# 6_SWITCHING.net
KiCad netlist of a schematic drawn in Altium Designer
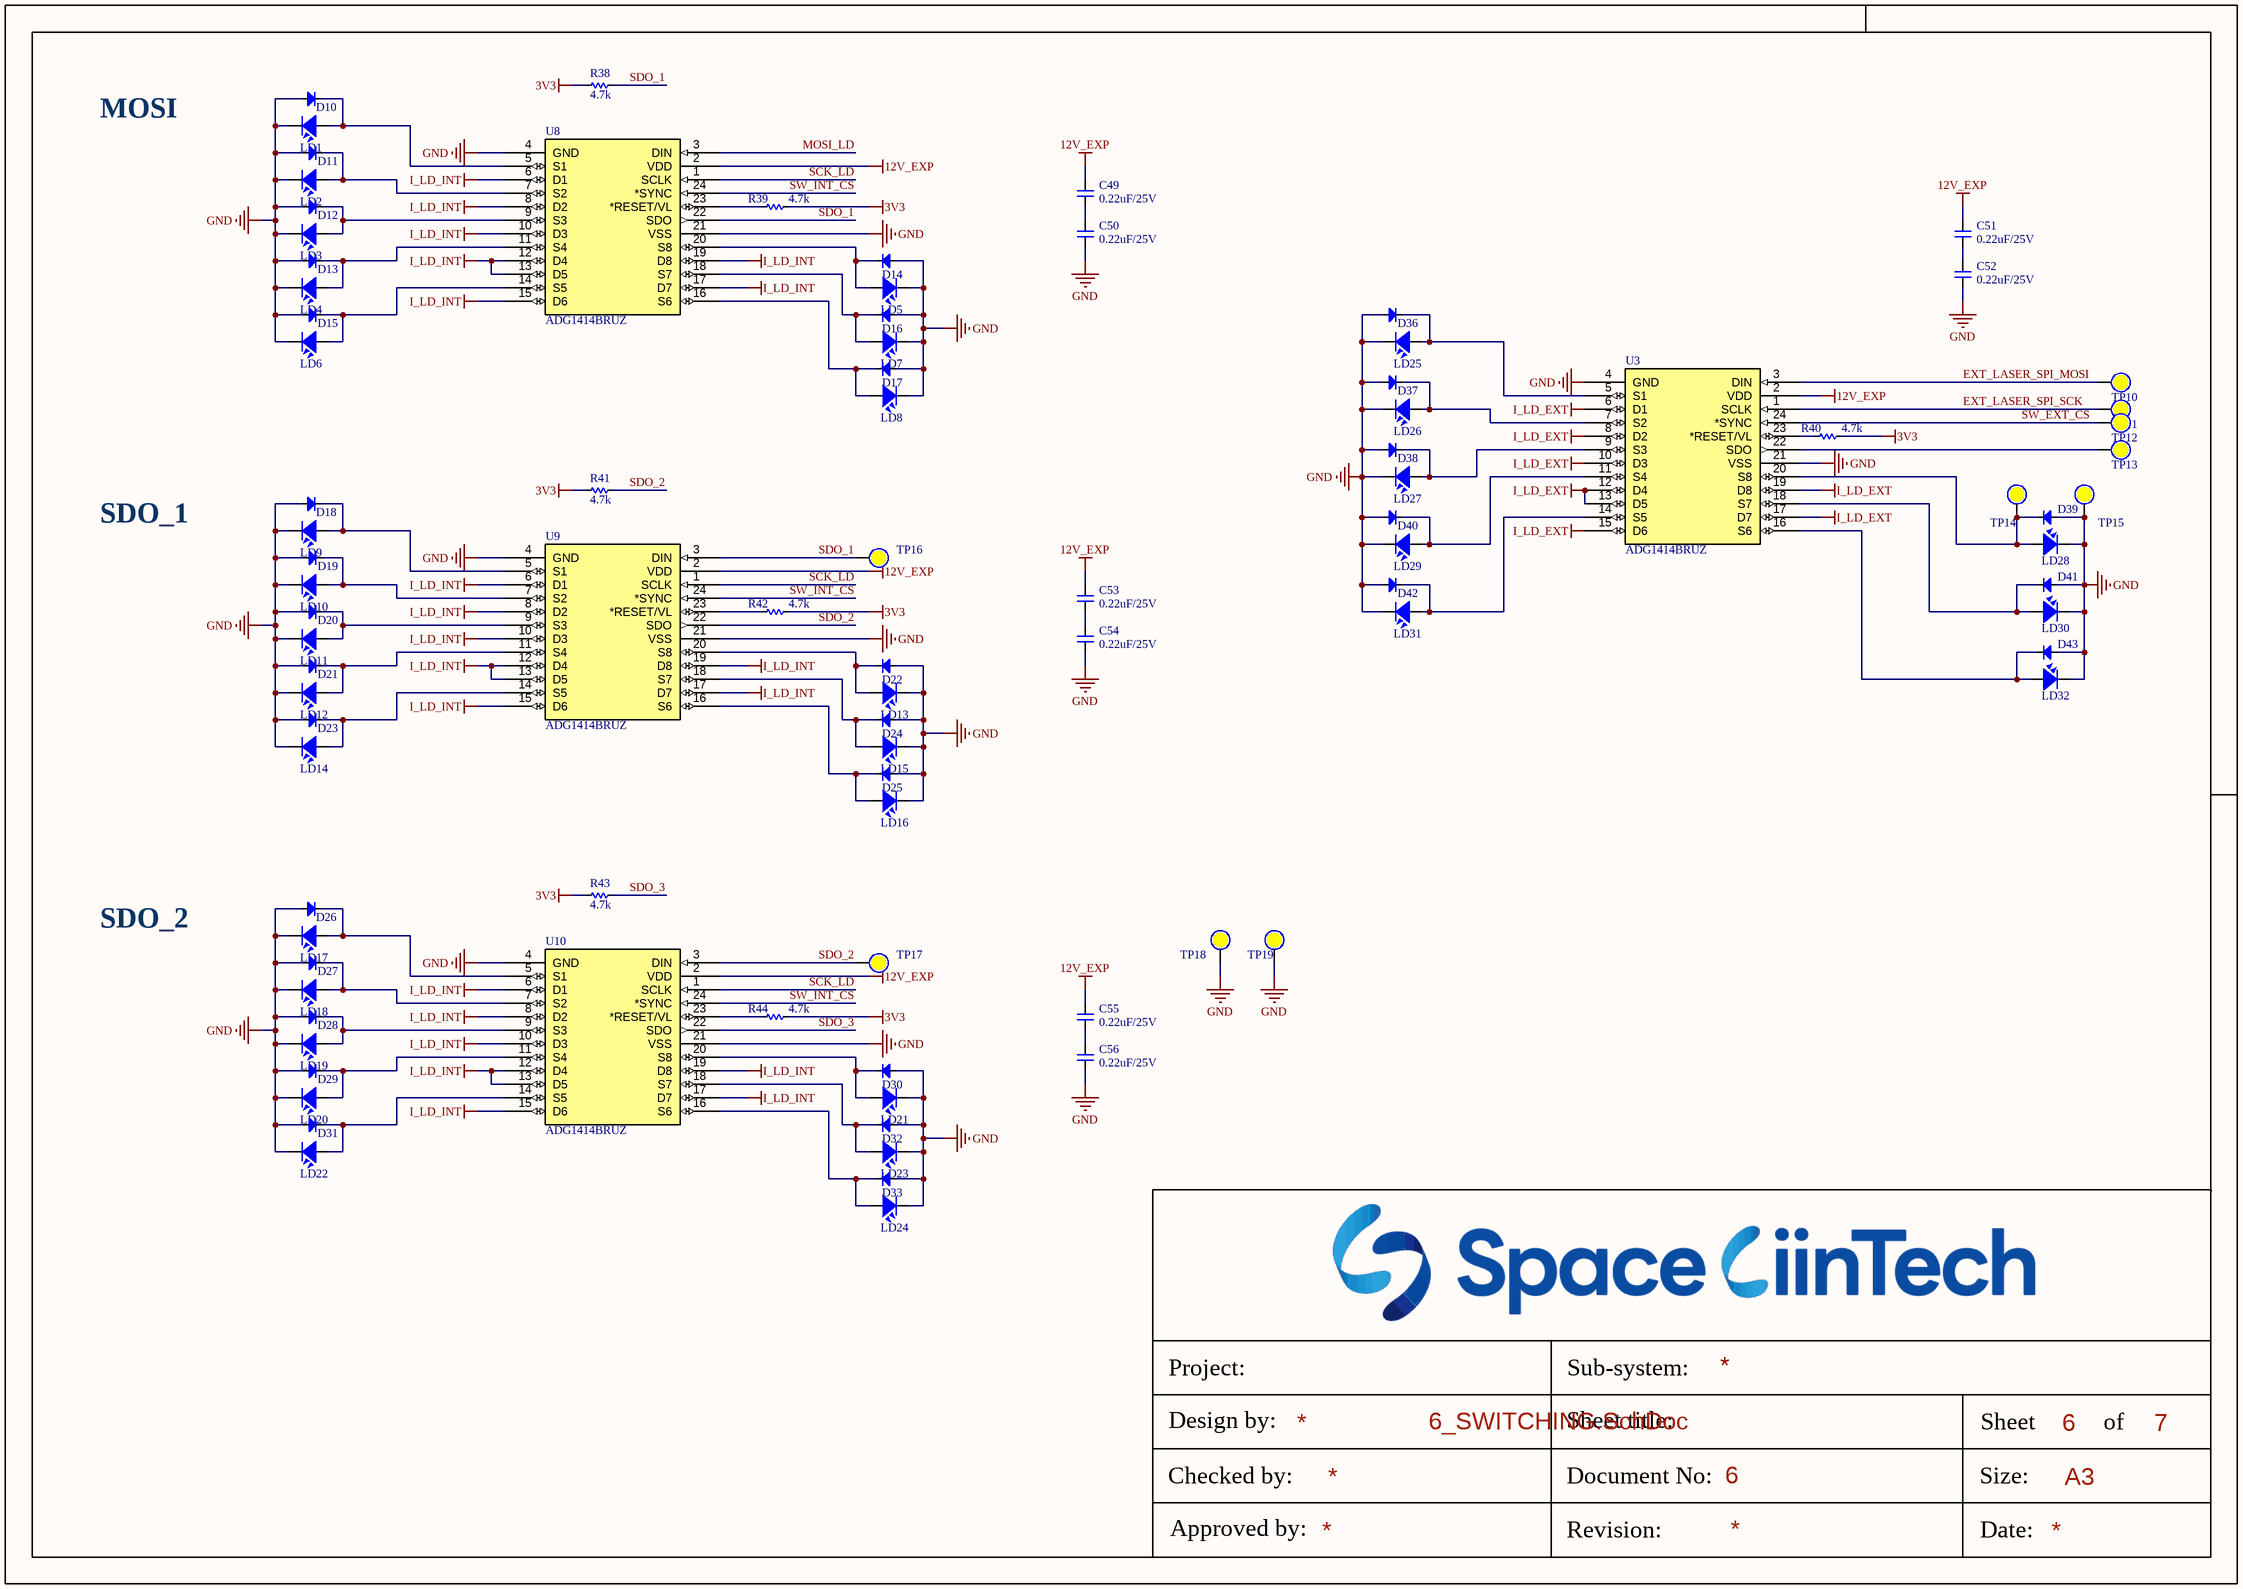
[diagram p0: 6_SWITCHING.SchDoc]

(export (version "E")
  (design (tool "Eeschema 10.0.6"))
  (components
    (comp (ref "C49")
      (value "0.22uF/25V")
      (footprint "CAP_C_1608X80")
      (description "CAP")
      (libsource (lib "LABLIB") (part "_CAP_C_2"))
    )
    (comp (ref "C50")
      (value "0.22uF/25V")
      (footprint "CAP_C_1608X80")
      (description "CAP")
      (libsource (lib "LABLIB") (part "_CAP_C_2"))
    )
    (comp (ref "C51")
      (value "0.22uF/25V")
      (footprint "CAP_C_1608X80")
      (description "CAP")
      (libsource (lib "LABLIB") (part "_CAP_C_2"))
    )
    (comp (ref "C52")
      (value "0.22uF/25V")
      (footprint "CAP_C_1608X80")
      (description "CAP")
      (libsource (lib "LABLIB") (part "_CAP_C_2"))
    )
    (comp (ref "C53")
      (value "0.22uF/25V")
      (footprint "CAP_C_1608X80")
      (description "CAP")
      (libsource (lib "LABLIB") (part "_CAP_C_2"))
    )
    (comp (ref "C54")
      (value "0.22uF/25V")
      (footprint "CAP_C_1608X80")
      (description "CAP")
      (libsource (lib "LABLIB") (part "_CAP_C_2"))
    )
    (comp (ref "C55")
      (value "0.22uF/25V")
      (footprint "CAP_C_1608X80")
      (description "CAP")
      (libsource (lib "LABLIB") (part "_CAP_C_2"))
    )
    (comp (ref "C56")
      (value "0.22uF/25V")
      (footprint "CAP_C_1608X80")
      (description "CAP")
      (libsource (lib "LABLIB") (part "_CAP_C_2"))
    )
    (comp (ref "D10")
      (value "1N4148W-TP")
      (footprint "SOD23")
      (fields (field (name "PUBLISHER") "Altium Limited"))
      (libsource (lib "LASER_LIB_SCHE") (part "Diode SMD"))
    )
    (comp (ref "D11")
      (value "1N4148W-TP")
      (footprint "SOD23")
      (fields (field (name "PUBLISHER") "Altium Limited"))
      (libsource (lib "LASER_LIB_SCHE") (part "Diode SMD"))
    )
    (comp (ref "D12")
      (value "1N4148W-TP")
      (footprint "SOD23")
      (fields (field (name "PUBLISHER") "Altium Limited"))
      (libsource (lib "LASER_LIB_SCHE") (part "Diode SMD"))
    )
    (comp (ref "D13")
      (value "1N4148W-TP")
      (footprint "SOD23")
      (fields (field (name "PUBLISHER") "Altium Limited"))
      (libsource (lib "LASER_LIB_SCHE") (part "Diode SMD"))
    )
    (comp (ref "D14")
      (value "1N4148W-TP")
      (footprint "SOD23")
      (fields (field (name "PUBLISHER") "Altium Limited"))
      (libsource (lib "LASER_LIB_SCHE") (part "Diode SMD"))
    )
    (comp (ref "D15")
      (value "1N4148W-TP")
      (footprint "SOD23")
      (fields (field (name "PUBLISHER") "Altium Limited"))
      (libsource (lib "LASER_LIB_SCHE") (part "Diode SMD"))
    )
    (comp (ref "D16")
      (value "1N4148W-TP")
      (footprint "SOD23")
      (fields (field (name "PUBLISHER") "Altium Limited"))
      (libsource (lib "LASER_LIB_SCHE") (part "Diode SMD"))
    )
    (comp (ref "D17")
      (value "1N4148W-TP")
      (footprint "SOD23")
      (fields (field (name "PUBLISHER") "Altium Limited"))
      (libsource (lib "LASER_LIB_SCHE") (part "Diode SMD"))
    )
    (comp (ref "D18")
      (value "1N4148W-TP")
      (footprint "SOD23")
      (fields (field (name "PUBLISHER") "Altium Limited"))
      (libsource (lib "LASER_LIB_SCHE") (part "Diode SMD"))
    )
    (comp (ref "D19")
      (value "1N4148W-TP")
      (footprint "SOD23")
      (fields (field (name "PUBLISHER") "Altium Limited"))
      (libsource (lib "LASER_LIB_SCHE") (part "Diode SMD"))
    )
    (comp (ref "D20")
      (value "1N4148W-TP")
      (footprint "SOD23")
      (fields (field (name "PUBLISHER") "Altium Limited"))
      (libsource (lib "LASER_LIB_SCHE") (part "Diode SMD"))
    )
    (comp (ref "D21")
      (value "1N4148W-TP")
      (footprint "SOD23")
      (fields (field (name "PUBLISHER") "Altium Limited"))
      (libsource (lib "LASER_LIB_SCHE") (part "Diode SMD"))
    )
    (comp (ref "D22")
      (value "1N4148W-TP")
      (footprint "SOD23")
      (fields (field (name "PUBLISHER") "Altium Limited"))
      (libsource (lib "LASER_LIB_SCHE") (part "Diode SMD"))
    )
    (comp (ref "D23")
      (value "1N4148W-TP")
      (footprint "SOD23")
      (fields (field (name "PUBLISHER") "Altium Limited"))
      (libsource (lib "LASER_LIB_SCHE") (part "Diode SMD"))
    )
    (comp (ref "D24")
      (value "1N4148W-TP")
      (footprint "SOD23")
      (fields (field (name "PUBLISHER") "Altium Limited"))
      (libsource (lib "LASER_LIB_SCHE") (part "Diode SMD"))
    )
    (comp (ref "D25")
      (value "1N4148W-TP")
      (footprint "SOD23")
      (fields (field (name "PUBLISHER") "Altium Limited"))
      (libsource (lib "LASER_LIB_SCHE") (part "Diode SMD"))
    )
    (comp (ref "D26")
      (value "1N4148W-TP")
      (footprint "SOD23")
      (fields (field (name "PUBLISHER") "Altium Limited"))
      (libsource (lib "LASER_LIB_SCHE") (part "Diode SMD"))
    )
    (comp (ref "D27")
      (value "1N4148W-TP")
      (footprint "SOD23")
      (fields (field (name "PUBLISHER") "Altium Limited"))
      (libsource (lib "LASER_LIB_SCHE") (part "Diode SMD"))
    )
    (comp (ref "D28")
      (value "1N4148W-TP")
      (footprint "SOD23")
      (fields (field (name "PUBLISHER") "Altium Limited"))
      (libsource (lib "LASER_LIB_SCHE") (part "Diode SMD"))
    )
    (comp (ref "D29")
      (value "1N4148W-TP")
      (footprint "SOD23")
      (fields (field (name "PUBLISHER") "Altium Limited"))
      (libsource (lib "LASER_LIB_SCHE") (part "Diode SMD"))
    )
    (comp (ref "D30")
      (value "1N4148W-TP")
      (footprint "SOD23")
      (fields (field (name "PUBLISHER") "Altium Limited"))
      (libsource (lib "LASER_LIB_SCHE") (part "Diode SMD"))
    )
    (comp (ref "D31")
      (value "1N4148W-TP")
      (footprint "SOD23")
      (fields (field (name "PUBLISHER") "Altium Limited"))
      (libsource (lib "LASER_LIB_SCHE") (part "Diode SMD"))
    )
    (comp (ref "D32")
      (value "1N4148W-TP")
      (footprint "SOD23")
      (fields (field (name "PUBLISHER") "Altium Limited"))
      (libsource (lib "LASER_LIB_SCHE") (part "Diode SMD"))
    )
    (comp (ref "D33")
      (value "1N4148W-TP")
      (footprint "SOD23")
      (fields (field (name "PUBLISHER") "Altium Limited"))
      (libsource (lib "LASER_LIB_SCHE") (part "Diode SMD"))
    )
    (comp (ref "D36")
      (value "1N4148W-TP")
      (footprint "SOD23")
      (fields (field (name "PUBLISHER") "Altium Limited"))
      (libsource (lib "LASER_LIB_SCHE") (part "Diode SMD"))
    )
    (comp (ref "D37")
      (value "1N4148W-TP")
      (footprint "SOD23")
      (fields (field (name "PUBLISHER") "Altium Limited"))
      (libsource (lib "LASER_LIB_SCHE") (part "Diode SMD"))
    )
    (comp (ref "D38")
      (value "1N4148W-TP")
      (footprint "SOD23")
      (fields (field (name "PUBLISHER") "Altium Limited"))
      (libsource (lib "LASER_LIB_SCHE") (part "Diode SMD"))
    )
    (comp (ref "D39")
      (value "1N4148W-TP")
      (footprint "SOD23")
      (fields (field (name "PUBLISHER") "Altium Limited"))
      (libsource (lib "LASER_LIB_SCHE") (part "Diode SMD"))
    )
    (comp (ref "D40")
      (value "1N4148W-TP")
      (footprint "SOD23")
      (fields (field (name "PUBLISHER") "Altium Limited"))
      (libsource (lib "LASER_LIB_SCHE") (part "Diode SMD"))
    )
    (comp (ref "D41")
      (value "1N4148W-TP")
      (footprint "SOD23")
      (fields (field (name "PUBLISHER") "Altium Limited"))
      (libsource (lib "LASER_LIB_SCHE") (part "Diode SMD"))
    )
    (comp (ref "D42")
      (value "1N4148W-TP")
      (footprint "SOD23")
      (fields (field (name "PUBLISHER") "Altium Limited"))
      (libsource (lib "LASER_LIB_SCHE") (part "Diode SMD"))
    )
    (comp (ref "D43")
      (value "1N4148W-TP")
      (footprint "SOD23")
      (fields (field (name "PUBLISHER") "Altium Limited"))
      (libsource (lib "LASER_LIB_SCHE") (part "Diode SMD"))
    )
    (comp (ref "LD1")
      (value "LaserDiode")
      (footprint "OPV302")
      (description "OPV302")
      (libsource (lib "LASER_LIB_SCHE") (part "LD"))
    )
    (comp (ref "LD2")
      (value "LaserDiode")
      (footprint "OPV302")
      (description "OPV302")
      (libsource (lib "LASER_LIB_SCHE") (part "LD"))
    )
    (comp (ref "LD3")
      (value "LaserDiode")
      (footprint "OPV302")
      (description "OPV302")
      (libsource (lib "LASER_LIB_SCHE") (part "LD"))
    )
    (comp (ref "LD4")
      (value "LaserDiode")
      (footprint "OPV302")
      (description "OPV302")
      (libsource (lib "LASER_LIB_SCHE") (part "LD"))
    )
    (comp (ref "LD5")
      (value "LaserDiode")
      (footprint "OPV302")
      (description "OPV302")
      (libsource (lib "LASER_LIB_SCHE") (part "LD"))
    )
    (comp (ref "LD6")
      (value "LaserDiode")
      (footprint "OPV302")
      (description "OPV302")
      (libsource (lib "LASER_LIB_SCHE") (part "LD"))
    )
    (comp (ref "LD7")
      (value "LaserDiode")
      (footprint "OPV302")
      (description "OPV302")
      (libsource (lib "LASER_LIB_SCHE") (part "LD"))
    )
    (comp (ref "LD8")
      (value "LaserDiode")
      (footprint "OPV302")
      (description "OPV302")
      (libsource (lib "LASER_LIB_SCHE") (part "LD"))
    )
    (comp (ref "LD9")
      (value "LaserDiode")
      (footprint "OPV302")
      (description "OPV302")
      (libsource (lib "LASER_LIB_SCHE") (part "LD"))
    )
    (comp (ref "LD10")
      (value "LaserDiode")
      (footprint "OPV302")
      (description "OPV302")
      (libsource (lib "LASER_LIB_SCHE") (part "LD"))
    )
    (comp (ref "LD11")
      (value "LaserDiode")
      (footprint "OPV302")
      (description "OPV302")
      (libsource (lib "LASER_LIB_SCHE") (part "LD"))
    )
    (comp (ref "LD12")
      (value "LaserDiode")
      (footprint "OPV302")
      (description "OPV302")
      (libsource (lib "LASER_LIB_SCHE") (part "LD"))
    )
    (comp (ref "LD13")
      (value "LaserDiode")
      (footprint "OPV302")
      (description "OPV302")
      (libsource (lib "LASER_LIB_SCHE") (part "LD"))
    )
    (comp (ref "LD14")
      (value "LaserDiode")
      (footprint "OPV302")
      (description "OPV302")
      (libsource (lib "LASER_LIB_SCHE") (part "LD"))
    )
    (comp (ref "LD15")
      (value "LaserDiode")
      (footprint "OPV302")
      (description "OPV302")
      (libsource (lib "LASER_LIB_SCHE") (part "LD"))
    )
    (comp (ref "LD16")
      (value "LaserDiode")
      (footprint "OPV302")
      (description "OPV302")
      (libsource (lib "LASER_LIB_SCHE") (part "LD"))
    )
    (comp (ref "LD17")
      (value "LaserDiode")
      (footprint "OPV302")
      (description "OPV302")
      (libsource (lib "LASER_LIB_SCHE") (part "LD"))
    )
    (comp (ref "LD18")
      (value "LaserDiode")
      (footprint "OPV302")
      (description "OPV302")
      (libsource (lib "LASER_LIB_SCHE") (part "LD"))
    )
    (comp (ref "LD19")
      (value "LaserDiode")
      (footprint "OPV302")
      (description "OPV302")
      (libsource (lib "LASER_LIB_SCHE") (part "LD"))
    )
    (comp (ref "LD20")
      (value "LaserDiode")
      (footprint "OPV302")
      (description "OPV302")
      (libsource (lib "LASER_LIB_SCHE") (part "LD"))
    )
    (comp (ref "LD21")
      (value "LaserDiode")
      (footprint "OPV302")
      (description "OPV302")
      (libsource (lib "LASER_LIB_SCHE") (part "LD"))
    )
    (comp (ref "LD22")
      (value "LaserDiode")
      (footprint "OPV302")
      (description "OPV302")
      (libsource (lib "LASER_LIB_SCHE") (part "LD"))
    )
    (comp (ref "LD23")
      (value "LaserDiode")
      (footprint "OPV302")
      (description "OPV302")
      (libsource (lib "LASER_LIB_SCHE") (part "LD"))
    )
    (comp (ref "LD24")
      (value "LaserDiode")
      (footprint "OPV302")
      (description "OPV302")
      (libsource (lib "LASER_LIB_SCHE") (part "LD"))
    )
    (comp (ref "LD25")
      (value "LaserDiode")
      (footprint "RLD65NZX1")
      (description "RLD65NZX1")
      (libsource (lib "LASER_LIB_SCHE") (part "LD_RLD65NZX1"))
    )
    (comp (ref "LD26")
      (value "LaserDiode")
      (footprint "RLD65NZX1")
      (description "RLD65NZX1")
      (libsource (lib "LASER_LIB_SCHE") (part "LD_RLD65NZX1"))
    )
    (comp (ref "LD27")
      (value "LaserDiode")
      (footprint "RLD65NZX1")
      (description "RLD65NZX1")
      (libsource (lib "LASER_LIB_SCHE") (part "LD_RLD65NZX1"))
    )
    (comp (ref "LD28")
      (value "LaserDiode")
      (footprint "RLD65NZX1")
      (description "RLD65NZX1")
      (libsource (lib "LASER_LIB_SCHE") (part "LD_RLD65NZX1"))
    )
    (comp (ref "LD29")
      (value "LaserDiode")
      (footprint "RLD65NZX1")
      (description "RLD65NZX1")
      (libsource (lib "LASER_LIB_SCHE") (part "LD_RLD65NZX1"))
    )
    (comp (ref "LD30")
      (value "LaserDiode")
      (footprint "RLD65NZX1")
      (description "RLD65NZX1")
      (libsource (lib "LASER_LIB_SCHE") (part "LD_RLD65NZX1"))
    )
    (comp (ref "LD31")
      (value "LaserDiode")
      (footprint "RLD65NZX1")
      (description "RLD65NZX1")
      (libsource (lib "LASER_LIB_SCHE") (part "LD_RLD65NZX1"))
    )
    (comp (ref "LD32")
      (value "LaserDiode")
      (footprint "RLD65NZX1")
      (description "RLD65NZX1")
      (libsource (lib "LASER_LIB_SCHE") (part "LD_RLD65NZX1"))
    )
    (comp (ref "R38")
      (value "4.7k")
      (footprint "RES_C_1608X60")
      (description "RES")
      (libsource (lib "LABLIB") (part "_RES_B_2"))
    )
    (comp (ref "R39")
      (value "4.7k")
      (footprint "RES_C_1608X60")
      (description "RES")
      (libsource (lib "LABLIB") (part "_RES_B_2"))
    )
    (comp (ref "R40")
      (value "4.7k")
      (footprint "RES_C_1608X60")
      (description "RES")
      (libsource (lib "LABLIB") (part "_RES_B_2"))
    )
    (comp (ref "R41")
      (value "4.7k")
      (footprint "RES_C_1608X60")
      (description "RES")
      (libsource (lib "LABLIB") (part "_RES_B_2"))
    )
    (comp (ref "R42")
      (value "4.7k")
      (footprint "RES_C_1608X60")
      (description "RES")
      (libsource (lib "LABLIB") (part "_RES_B_2"))
    )
    (comp (ref "R43")
      (value "4.7k")
      (footprint "RES_C_1608X60")
      (description "RES")
      (libsource (lib "LABLIB") (part "_RES_B_2"))
    )
    (comp (ref "R44")
      (value "4.7k")
      (footprint "RES_C_1608X60")
      (description "RES")
      (libsource (lib "LABLIB") (part "_RES_B_2"))
    )
    (comp (ref "TP10")
      (value "~")
      (footprint "Testpoint_50")
      (description "Test Point")
      (libsource (lib "LASER_LIB_SCHE") (part "Test Point"))
    )
    (comp (ref "TP11")
      (value "~")
      (footprint "Testpoint_50")
      (description "Test Point")
      (libsource (lib "LASER_LIB_SCHE") (part "Test Point"))
    )
    (comp (ref "TP12")
      (value "~")
      (footprint "Testpoint_50")
      (description "Test Point")
      (libsource (lib "LASER_LIB_SCHE") (part "Test Point"))
    )
    (comp (ref "TP13")
      (value "~")
      (footprint "Testpoint_50")
      (description "Test Point")
      (libsource (lib "LASER_LIB_SCHE") (part "Test Point"))
    )
    (comp (ref "TP14")
      (value "~")
      (footprint "Testpoint_50")
      (description "Test Point")
      (libsource (lib "") (part "Test Point_1"))
    )
    (comp (ref "TP15")
      (value "~")
      (footprint "Testpoint_50")
      (description "Test Point")
      (libsource (lib "") (part "Test Point_1"))
    )
    (comp (ref "TP16")
      (value "~")
      (footprint "Testpoint_50")
      (description "Test Point")
      (libsource (lib "LASER_LIB_SCHE") (part "Test Point"))
    )
    (comp (ref "TP17")
      (value "~")
      (footprint "Testpoint_50")
      (description "Test Point")
      (libsource (lib "LASER_LIB_SCHE") (part "Test Point"))
    )
    (comp (ref "TP18")
      (value "~")
      (footprint "Testpoint_50")
      (description "Test Point")
      (libsource (lib "") (part "Test Point_1"))
    )
    (comp (ref "TP19")
      (value "~")
      (footprint "Testpoint_50")
      (description "Test Point")
      (libsource (lib "") (part "Test Point_1"))
    )
    (comp (ref "U3")
      (value "ADG1414BRUZ")
      (footprint "TSSOP24")
      (libsource (lib "LASER_LIB_SCHE") (part "ADG1414BRUZ"))
    )
    (comp (ref "U8")
      (value "ADG1414BRUZ")
      (footprint "TSSOP24")
      (libsource (lib "LASER_LIB_SCHE") (part "ADG1414BRUZ"))
    )
    (comp (ref "U9")
      (value "ADG1414BRUZ")
      (footprint "TSSOP24")
      (libsource (lib "LASER_LIB_SCHE") (part "ADG1414BRUZ"))
    )
    (comp (ref "U10")
      (value "ADG1414BRUZ")
      (footprint "TSSOP24")
      (libsource (lib "LASER_LIB_SCHE") (part "ADG1414BRUZ"))
    )
  )
  (nets
    (net (code "1") (name "/EXT_LASER_SPI_MOSI") (class "Default")
      (node (ref "TP10") (pin "1") (pinfunction "1_1") (pintype "passive"))
      (node (ref "U3") (pin "3") (pinfunction "DIN_3") (pintype "input"))
    )
    (net (code "2") (name "/EXT_LASER_SPI_SCK") (class "Default")
      (node (ref "TP11") (pin "1") (pinfunction "1_1") (pintype "passive"))
      (node (ref "U3") (pin "1") (pinfunction "SCLK_1") (pintype "input"))
    )
    (net (code "3") (name "/MOSI_LD") (class "Default")
      (node (ref "U8") (pin "3") (pinfunction "DIN_3") (pintype "input"))
    )
    (net (code "4") (name "/SCK_LD") (class "Default")
      (node (ref "U10") (pin "1") (pinfunction "SCLK_1") (pintype "input"))
      (node (ref "U8") (pin "1") (pinfunction "SCLK_1") (pintype "input"))
      (node (ref "U9") (pin "1") (pinfunction "SCLK_1") (pintype "input"))
    )
    (net (code "5") (name "/SDO_1") (class "Default")
      (node (ref "R38") (pin "2") (pinfunction "2_2") (pintype "passive"))
      (node (ref "TP16") (pin "1") (pinfunction "1_1") (pintype "passive"))
      (node (ref "U8") (pin "22") (pinfunction "SDO_22") (pintype "output"))
      (node (ref "U9") (pin "3") (pinfunction "DIN_3") (pintype "input"))
    )
    (net (code "6") (name "/SDO_2") (class "Default")
      (node (ref "R41") (pin "2") (pinfunction "2_2") (pintype "passive"))
      (node (ref "TP17") (pin "1") (pinfunction "1_1") (pintype "passive"))
      (node (ref "U10") (pin "3") (pinfunction "DIN_3") (pintype "input"))
      (node (ref "U9") (pin "22") (pinfunction "SDO_22") (pintype "output"))
    )
    (net (code "7") (name "/SDO_3") (class "Default")
      (node (ref "R43") (pin "2") (pinfunction "2_2") (pintype "passive"))
      (node (ref "U10") (pin "22") (pinfunction "SDO_22") (pintype "output"))
    )
    (net (code "8") (name "/SW_EXT_CS") (class "Default")
      (node (ref "TP12") (pin "1") (pinfunction "1_1") (pintype "passive"))
      (node (ref "U3") (pin "24") (pinfunction "*SYNC_24") (pintype "input"))
    )
    (net (code "9") (name "/SW_INT_CS") (class "Default")
      (node (ref "U10") (pin "24") (pinfunction "*SYNC_24") (pintype "input"))
      (node (ref "U8") (pin "24") (pinfunction "*SYNC_24") (pintype "input"))
      (node (ref "U9") (pin "24") (pinfunction "*SYNC_24") (pintype "input"))
    )
    (net (code "10") (name "3V3") (class "Default")
      (node (ref "R38") (pin "1") (pinfunction "1_1") (pintype "passive"))
      (node (ref "R39") (pin "2") (pinfunction "2_2") (pintype "passive"))
      (node (ref "R40") (pin "2") (pinfunction "2_2") (pintype "passive"))
      (node (ref "R41") (pin "1") (pinfunction "1_1") (pintype "passive"))
      (node (ref "R42") (pin "2") (pinfunction "2_2") (pintype "passive"))
      (node (ref "R43") (pin "1") (pinfunction "1_1") (pintype "passive"))
      (node (ref "R44") (pin "2") (pinfunction "2_2") (pintype "passive"))
    )
    (net (code "11") (name "12V_EXP") (class "Default")
      (node (ref "C49") (pin "2") (pinfunction "2_2") (pintype "passive"))
      (node (ref "C51") (pin "2") (pinfunction "2_2") (pintype "passive"))
      (node (ref "C53") (pin "2") (pinfunction "2_2") (pintype "passive"))
      (node (ref "C55") (pin "2") (pinfunction "2_2") (pintype "passive"))
      (node (ref "U10") (pin "2") (pinfunction "VDD_2") (pintype "power_in"))
      (node (ref "U3") (pin "2") (pinfunction "VDD_2") (pintype "power_in"))
      (node (ref "U8") (pin "2") (pinfunction "VDD_2") (pintype "power_in"))
      (node (ref "U9") (pin "2") (pinfunction "VDD_2") (pintype "power_in"))
    )
    (net (code "12") (name "GND") (class "Default")
      (node (ref "C50") (pin "1") (pinfunction "1_1") (pintype "passive"))
      (node (ref "C52") (pin "1") (pinfunction "1_1") (pintype "passive"))
      (node (ref "C54") (pin "1") (pinfunction "1_1") (pintype "passive"))
      (node (ref "C56") (pin "1") (pinfunction "1_1") (pintype "passive"))
      (node (ref "D10") (pin "1") (pinfunction "A_1") (pintype "passive"))
      (node (ref "D11") (pin "1") (pinfunction "A_1") (pintype "passive"))
      (node (ref "D12") (pin "1") (pinfunction "A_1") (pintype "passive"))
      (node (ref "D13") (pin "1") (pinfunction "A_1") (pintype "passive"))
      (node (ref "D14") (pin "1") (pinfunction "A_1") (pintype "passive"))
      (node (ref "D15") (pin "1") (pinfunction "A_1") (pintype "passive"))
      (node (ref "D16") (pin "1") (pinfunction "A_1") (pintype "passive"))
      (node (ref "D17") (pin "1") (pinfunction "A_1") (pintype "passive"))
      (node (ref "D18") (pin "1") (pinfunction "A_1") (pintype "passive"))
      (node (ref "D19") (pin "1") (pinfunction "A_1") (pintype "passive"))
      (node (ref "D20") (pin "1") (pinfunction "A_1") (pintype "passive"))
      (node (ref "D21") (pin "1") (pinfunction "A_1") (pintype "passive"))
      (node (ref "D22") (pin "1") (pinfunction "A_1") (pintype "passive"))
      (node (ref "D23") (pin "1") (pinfunction "A_1") (pintype "passive"))
      (node (ref "D24") (pin "1") (pinfunction "A_1") (pintype "passive"))
      (node (ref "D25") (pin "1") (pinfunction "A_1") (pintype "passive"))
      (node (ref "D26") (pin "1") (pinfunction "A_1") (pintype "passive"))
      (node (ref "D27") (pin "1") (pinfunction "A_1") (pintype "passive"))
      (node (ref "D28") (pin "1") (pinfunction "A_1") (pintype "passive"))
      (node (ref "D29") (pin "1") (pinfunction "A_1") (pintype "passive"))
      (node (ref "D30") (pin "1") (pinfunction "A_1") (pintype "passive"))
      (node (ref "D31") (pin "1") (pinfunction "A_1") (pintype "passive"))
      (node (ref "D32") (pin "1") (pinfunction "A_1") (pintype "passive"))
      (node (ref "D33") (pin "1") (pinfunction "A_1") (pintype "passive"))
      (node (ref "D36") (pin "1") (pinfunction "A_1") (pintype "passive"))
      (node (ref "D37") (pin "1") (pinfunction "A_1") (pintype "passive"))
      (node (ref "D38") (pin "1") (pinfunction "A_1") (pintype "passive"))
      (node (ref "D39") (pin "1") (pinfunction "A_1") (pintype "passive"))
      (node (ref "D40") (pin "1") (pinfunction "A_1") (pintype "passive"))
      (node (ref "D41") (pin "1") (pinfunction "A_1") (pintype "passive"))
      (node (ref "D42") (pin "1") (pinfunction "A_1") (pintype "passive"))
      (node (ref "D43") (pin "1") (pinfunction "A_1") (pintype "passive"))
      (node (ref "LD1") (pin "2") (pinfunction "2_2") (pintype "passive"))
      (node (ref "LD10") (pin "2") (pinfunction "2_2") (pintype "passive"))
      (node (ref "LD11") (pin "2") (pinfunction "2_2") (pintype "passive"))
      (node (ref "LD12") (pin "2") (pinfunction "2_2") (pintype "passive"))
      (node (ref "LD13") (pin "2") (pinfunction "2_2") (pintype "passive"))
      (node (ref "LD14") (pin "2") (pinfunction "2_2") (pintype "passive"))
      (node (ref "LD15") (pin "2") (pinfunction "2_2") (pintype "passive"))
      (node (ref "LD16") (pin "2") (pinfunction "2_2") (pintype "passive"))
      (node (ref "LD17") (pin "2") (pinfunction "2_2") (pintype "passive"))
      (node (ref "LD18") (pin "2") (pinfunction "2_2") (pintype "passive"))
      (node (ref "LD19") (pin "2") (pinfunction "2_2") (pintype "passive"))
      (node (ref "LD2") (pin "2") (pinfunction "2_2") (pintype "passive"))
      (node (ref "LD20") (pin "2") (pinfunction "2_2") (pintype "passive"))
      (node (ref "LD21") (pin "2") (pinfunction "2_2") (pintype "passive"))
      (node (ref "LD22") (pin "2") (pinfunction "2_2") (pintype "passive"))
      (node (ref "LD23") (pin "2") (pinfunction "2_2") (pintype "passive"))
      (node (ref "LD24") (pin "2") (pinfunction "2_2") (pintype "passive"))
      (node (ref "LD25") (pin "1") (pinfunction "1_1") (pintype "passive"))
      (node (ref "LD26") (pin "1") (pinfunction "1_1") (pintype "passive"))
      (node (ref "LD27") (pin "1") (pinfunction "1_1") (pintype "passive"))
      (node (ref "LD28") (pin "1") (pinfunction "1_1") (pintype "passive"))
      (node (ref "LD29") (pin "1") (pinfunction "1_1") (pintype "passive"))
      (node (ref "LD3") (pin "2") (pinfunction "2_2") (pintype "passive"))
      (node (ref "LD30") (pin "1") (pinfunction "1_1") (pintype "passive"))
      (node (ref "LD31") (pin "1") (pinfunction "1_1") (pintype "passive"))
      (node (ref "LD32") (pin "1") (pinfunction "1_1") (pintype "passive"))
      (node (ref "LD4") (pin "2") (pinfunction "2_2") (pintype "passive"))
      (node (ref "LD5") (pin "2") (pinfunction "2_2") (pintype "passive"))
      (node (ref "LD6") (pin "2") (pinfunction "2_2") (pintype "passive"))
      (node (ref "LD7") (pin "2") (pinfunction "2_2") (pintype "passive"))
      (node (ref "LD8") (pin "2") (pinfunction "2_2") (pintype "passive"))
      (node (ref "LD9") (pin "2") (pinfunction "2_2") (pintype "passive"))
      (node (ref "TP15") (pin "1") (pinfunction "1_1") (pintype "passive"))
      (node (ref "TP18") (pin "1") (pinfunction "1_1") (pintype "passive"))
      (node (ref "TP19") (pin "1") (pinfunction "1_1") (pintype "passive"))
      (node (ref "U10") (pin "21") (pinfunction "VSS_21") (pintype "power_in"))
      (node (ref "U10") (pin "4") (pinfunction "GND_4") (pintype "power_in"))
      (node (ref "U3") (pin "21") (pinfunction "VSS_21") (pintype "power_in"))
      (node (ref "U3") (pin "4") (pinfunction "GND_4") (pintype "power_in"))
      (node (ref "U8") (pin "21") (pinfunction "VSS_21") (pintype "power_in"))
      (node (ref "U8") (pin "4") (pinfunction "GND_4") (pintype "power_in"))
      (node (ref "U9") (pin "21") (pinfunction "VSS_21") (pintype "power_in"))
      (node (ref "U9") (pin "4") (pinfunction "GND_4") (pintype "power_in"))
    )
    (net (code "13") (name "I_LD_EXT") (class "Default")
      (node (ref "U3") (pin "10") (pinfunction "D3_10") (pintype "bidirectional"))
      (node (ref "U3") (pin "12") (pinfunction "D4_12") (pintype "bidirectional"))
      (node (ref "U3") (pin "13") (pinfunction "D5_13") (pintype "bidirectional"))
      (node (ref "U3") (pin "15") (pinfunction "D6_15") (pintype "bidirectional"))
      (node (ref "U3") (pin "17") (pinfunction "D7_17") (pintype "bidirectional"))
      (node (ref "U3") (pin "19") (pinfunction "D8_19") (pintype "bidirectional"))
      (node (ref "U3") (pin "6") (pinfunction "D1_6") (pintype "bidirectional"))
      (node (ref "U3") (pin "8") (pinfunction "D2_8") (pintype "bidirectional"))
    )
    (net (code "14") (name "I_LD_INT") (class "Default")
      (node (ref "U10") (pin "10") (pinfunction "D3_10") (pintype "bidirectional"))
      (node (ref "U10") (pin "12") (pinfunction "D4_12") (pintype "bidirectional"))
      (node (ref "U10") (pin "13") (pinfunction "D5_13") (pintype "bidirectional"))
      (node (ref "U10") (pin "15") (pinfunction "D6_15") (pintype "bidirectional"))
      (node (ref "U10") (pin "17") (pinfunction "D7_17") (pintype "bidirectional"))
      (node (ref "U10") (pin "19") (pinfunction "D8_19") (pintype "bidirectional"))
      (node (ref "U10") (pin "6") (pinfunction "D1_6") (pintype "bidirectional"))
      (node (ref "U10") (pin "8") (pinfunction "D2_8") (pintype "bidirectional"))
      (node (ref "U8") (pin "10") (pinfunction "D3_10") (pintype "bidirectional"))
      (node (ref "U8") (pin "12") (pinfunction "D4_12") (pintype "bidirectional"))
      (node (ref "U8") (pin "13") (pinfunction "D5_13") (pintype "bidirectional"))
      (node (ref "U8") (pin "15") (pinfunction "D6_15") (pintype "bidirectional"))
      (node (ref "U8") (pin "17") (pinfunction "D7_17") (pintype "bidirectional"))
      (node (ref "U8") (pin "19") (pinfunction "D8_19") (pintype "bidirectional"))
      (node (ref "U8") (pin "6") (pinfunction "D1_6") (pintype "bidirectional"))
      (node (ref "U8") (pin "8") (pinfunction "D2_8") (pintype "bidirectional"))
      (node (ref "U9") (pin "10") (pinfunction "D3_10") (pintype "bidirectional"))
      (node (ref "U9") (pin "12") (pinfunction "D4_12") (pintype "bidirectional"))
      (node (ref "U9") (pin "13") (pinfunction "D5_13") (pintype "bidirectional"))
      (node (ref "U9") (pin "15") (pinfunction "D6_15") (pintype "bidirectional"))
      (node (ref "U9") (pin "17") (pinfunction "D7_17") (pintype "bidirectional"))
      (node (ref "U9") (pin "19") (pinfunction "D8_19") (pintype "bidirectional"))
      (node (ref "U9") (pin "6") (pinfunction "D1_6") (pintype "bidirectional"))
      (node (ref "U9") (pin "8") (pinfunction "D2_8") (pintype "bidirectional"))
    )
    (net (code "15") (name "Net-(C49-Pad1)") (class "Default")
      (node (ref "C49") (pin "1") (pinfunction "1_1") (pintype "passive"))
      (node (ref "C50") (pin "2") (pinfunction "2_2") (pintype "passive"))
    )
    (net (code "16") (name "Net-(C51-Pad1)") (class "Default")
      (node (ref "C51") (pin "1") (pinfunction "1_1") (pintype "passive"))
      (node (ref "C52") (pin "2") (pinfunction "2_2") (pintype "passive"))
    )
    (net (code "17") (name "Net-(C53-Pad1)") (class "Default")
      (node (ref "C53") (pin "1") (pinfunction "1_1") (pintype "passive"))
      (node (ref "C54") (pin "2") (pinfunction "2_2") (pintype "passive"))
    )
    (net (code "18") (name "Net-(C55-Pad1)") (class "Default")
      (node (ref "C55") (pin "1") (pinfunction "1_1") (pintype "passive"))
      (node (ref "C56") (pin "2") (pinfunction "2_2") (pintype "passive"))
    )
    (net (code "19") (name "Net-(D10-K)") (class "Default")
      (node (ref "D10") (pin "2") (pinfunction "K_2") (pintype "passive"))
      (node (ref "LD1") (pin "1") (pinfunction "1_1") (pintype "passive"))
      (node (ref "U8") (pin "5") (pinfunction "S1_5") (pintype "bidirectional"))
    )
    (net (code "20") (name "Net-(D11-K)") (class "Default")
      (node (ref "D11") (pin "2") (pinfunction "K_2") (pintype "passive"))
      (node (ref "LD2") (pin "1") (pinfunction "1_1") (pintype "passive"))
      (node (ref "U8") (pin "7") (pinfunction "S2_7") (pintype "bidirectional"))
    )
    (net (code "21") (name "Net-(D12-K)") (class "Default")
      (node (ref "D12") (pin "2") (pinfunction "K_2") (pintype "passive"))
      (node (ref "LD3") (pin "1") (pinfunction "1_1") (pintype "passive"))
      (node (ref "U8") (pin "9") (pinfunction "S3_9") (pintype "bidirectional"))
    )
    (net (code "22") (name "Net-(D13-K)") (class "Default")
      (node (ref "D13") (pin "2") (pinfunction "K_2") (pintype "passive"))
      (node (ref "LD4") (pin "1") (pinfunction "1_1") (pintype "passive"))
      (node (ref "U8") (pin "11") (pinfunction "S4_11") (pintype "bidirectional"))
    )
    (net (code "23") (name "Net-(D14-K)") (class "Default")
      (node (ref "D14") (pin "2") (pinfunction "K_2") (pintype "passive"))
      (node (ref "LD5") (pin "1") (pinfunction "1_1") (pintype "passive"))
      (node (ref "U8") (pin "20") (pinfunction "S8_20") (pintype "bidirectional"))
    )
    (net (code "24") (name "Net-(D15-K)") (class "Default")
      (node (ref "D15") (pin "2") (pinfunction "K_2") (pintype "passive"))
      (node (ref "LD6") (pin "1") (pinfunction "1_1") (pintype "passive"))
      (node (ref "U8") (pin "14") (pinfunction "S5_14") (pintype "bidirectional"))
    )
    (net (code "25") (name "Net-(D16-K)") (class "Default")
      (node (ref "D16") (pin "2") (pinfunction "K_2") (pintype "passive"))
      (node (ref "LD7") (pin "1") (pinfunction "1_1") (pintype "passive"))
      (node (ref "U8") (pin "18") (pinfunction "S7_18") (pintype "bidirectional"))
    )
    (net (code "26") (name "Net-(D17-K)") (class "Default")
      (node (ref "D17") (pin "2") (pinfunction "K_2") (pintype "passive"))
      (node (ref "LD8") (pin "1") (pinfunction "1_1") (pintype "passive"))
      (node (ref "U8") (pin "16") (pinfunction "S6_16") (pintype "bidirectional"))
    )
    (net (code "27") (name "Net-(D18-K)") (class "Default")
      (node (ref "D18") (pin "2") (pinfunction "K_2") (pintype "passive"))
      (node (ref "LD9") (pin "1") (pinfunction "1_1") (pintype "passive"))
      (node (ref "U9") (pin "5") (pinfunction "S1_5") (pintype "bidirectional"))
    )
    (net (code "28") (name "Net-(D19-K)") (class "Default")
      (node (ref "D19") (pin "2") (pinfunction "K_2") (pintype "passive"))
      (node (ref "LD10") (pin "1") (pinfunction "1_1") (pintype "passive"))
      (node (ref "U9") (pin "7") (pinfunction "S2_7") (pintype "bidirectional"))
    )
    (net (code "29") (name "Net-(D20-K)") (class "Default")
      (node (ref "D20") (pin "2") (pinfunction "K_2") (pintype "passive"))
      (node (ref "LD11") (pin "1") (pinfunction "1_1") (pintype "passive"))
      (node (ref "U9") (pin "9") (pinfunction "S3_9") (pintype "bidirectional"))
    )
    (net (code "30") (name "Net-(D21-K)") (class "Default")
      (node (ref "D21") (pin "2") (pinfunction "K_2") (pintype "passive"))
      (node (ref "LD12") (pin "1") (pinfunction "1_1") (pintype "passive"))
      (node (ref "U9") (pin "11") (pinfunction "S4_11") (pintype "bidirectional"))
    )
    (net (code "31") (name "Net-(D22-K)") (class "Default")
      (node (ref "D22") (pin "2") (pinfunction "K_2") (pintype "passive"))
      (node (ref "LD13") (pin "1") (pinfunction "1_1") (pintype "passive"))
      (node (ref "U9") (pin "20") (pinfunction "S8_20") (pintype "bidirectional"))
    )
    (net (code "32") (name "Net-(D23-K)") (class "Default")
      (node (ref "D23") (pin "2") (pinfunction "K_2") (pintype "passive"))
      (node (ref "LD14") (pin "1") (pinfunction "1_1") (pintype "passive"))
      (node (ref "U9") (pin "14") (pinfunction "S5_14") (pintype "bidirectional"))
    )
    (net (code "33") (name "Net-(D24-K)") (class "Default")
      (node (ref "D24") (pin "2") (pinfunction "K_2") (pintype "passive"))
      (node (ref "LD15") (pin "1") (pinfunction "1_1") (pintype "passive"))
      (node (ref "U9") (pin "18") (pinfunction "S7_18") (pintype "bidirectional"))
    )
    (net (code "34") (name "Net-(D25-K)") (class "Default")
      (node (ref "D25") (pin "2") (pinfunction "K_2") (pintype "passive"))
      (node (ref "LD16") (pin "1") (pinfunction "1_1") (pintype "passive"))
      (node (ref "U9") (pin "16") (pinfunction "S6_16") (pintype "bidirectional"))
    )
    (net (code "35") (name "Net-(D26-K)") (class "Default")
      (node (ref "D26") (pin "2") (pinfunction "K_2") (pintype "passive"))
      (node (ref "LD17") (pin "1") (pinfunction "1_1") (pintype "passive"))
      (node (ref "U10") (pin "5") (pinfunction "S1_5") (pintype "bidirectional"))
    )
    (net (code "36") (name "Net-(D27-K)") (class "Default")
      (node (ref "D27") (pin "2") (pinfunction "K_2") (pintype "passive"))
      (node (ref "LD18") (pin "1") (pinfunction "1_1") (pintype "passive"))
      (node (ref "U10") (pin "7") (pinfunction "S2_7") (pintype "bidirectional"))
    )
    (net (code "37") (name "Net-(D28-K)") (class "Default")
      (node (ref "D28") (pin "2") (pinfunction "K_2") (pintype "passive"))
      (node (ref "LD19") (pin "1") (pinfunction "1_1") (pintype "passive"))
      (node (ref "U10") (pin "9") (pinfunction "S3_9") (pintype "bidirectional"))
    )
    (net (code "38") (name "Net-(D29-K)") (class "Default")
      (node (ref "D29") (pin "2") (pinfunction "K_2") (pintype "passive"))
      (node (ref "LD20") (pin "1") (pinfunction "1_1") (pintype "passive"))
      (node (ref "U10") (pin "11") (pinfunction "S4_11") (pintype "bidirectional"))
    )
    (net (code "39") (name "Net-(D30-K)") (class "Default")
      (node (ref "D30") (pin "2") (pinfunction "K_2") (pintype "passive"))
      (node (ref "LD21") (pin "1") (pinfunction "1_1") (pintype "passive"))
      (node (ref "U10") (pin "20") (pinfunction "S8_20") (pintype "bidirectional"))
    )
    (net (code "40") (name "Net-(D31-K)") (class "Default")
      (node (ref "D31") (pin "2") (pinfunction "K_2") (pintype "passive"))
      (node (ref "LD22") (pin "1") (pinfunction "1_1") (pintype "passive"))
      (node (ref "U10") (pin "14") (pinfunction "S5_14") (pintype "bidirectional"))
    )
    (net (code "41") (name "Net-(D32-K)") (class "Default")
      (node (ref "D32") (pin "2") (pinfunction "K_2") (pintype "passive"))
      (node (ref "LD23") (pin "1") (pinfunction "1_1") (pintype "passive"))
      (node (ref "U10") (pin "18") (pinfunction "S7_18") (pintype "bidirectional"))
    )
    (net (code "42") (name "Net-(D33-K)") (class "Default")
      (node (ref "D33") (pin "2") (pinfunction "K_2") (pintype "passive"))
      (node (ref "LD24") (pin "1") (pinfunction "1_1") (pintype "passive"))
      (node (ref "U10") (pin "16") (pinfunction "S6_16") (pintype "bidirectional"))
    )
    (net (code "43") (name "Net-(D36-K)") (class "Default")
      (node (ref "D36") (pin "2") (pinfunction "K_2") (pintype "passive"))
      (node (ref "LD25") (pin "3") (pinfunction "3_3") (pintype "passive"))
      (node (ref "U3") (pin "5") (pinfunction "S1_5") (pintype "bidirectional"))
    )
    (net (code "44") (name "Net-(D37-K)") (class "Default")
      (node (ref "D37") (pin "2") (pinfunction "K_2") (pintype "passive"))
      (node (ref "LD26") (pin "3") (pinfunction "3_3") (pintype "passive"))
      (node (ref "U3") (pin "7") (pinfunction "S2_7") (pintype "bidirectional"))
    )
    (net (code "45") (name "Net-(D38-K)") (class "Default")
      (node (ref "D38") (pin "2") (pinfunction "K_2") (pintype "passive"))
      (node (ref "LD27") (pin "3") (pinfunction "3_3") (pintype "passive"))
      (node (ref "U3") (pin "9") (pinfunction "S3_9") (pintype "bidirectional"))
    )
    (net (code "46") (name "Net-(D39-K)") (class "Default")
      (node (ref "D39") (pin "2") (pinfunction "K_2") (pintype "passive"))
      (node (ref "LD28") (pin "3") (pinfunction "3_3") (pintype "passive"))
      (node (ref "TP14") (pin "1") (pinfunction "1_1") (pintype "passive"))
      (node (ref "U3") (pin "20") (pinfunction "S8_20") (pintype "bidirectional"))
    )
    (net (code "47") (name "Net-(D40-K)") (class "Default")
      (node (ref "D40") (pin "2") (pinfunction "K_2") (pintype "passive"))
      (node (ref "LD29") (pin "3") (pinfunction "3_3") (pintype "passive"))
      (node (ref "U3") (pin "11") (pinfunction "S4_11") (pintype "bidirectional"))
    )
    (net (code "48") (name "Net-(D41-K)") (class "Default")
      (node (ref "D41") (pin "2") (pinfunction "K_2") (pintype "passive"))
      (node (ref "LD30") (pin "3") (pinfunction "3_3") (pintype "passive"))
      (node (ref "U3") (pin "18") (pinfunction "S7_18") (pintype "bidirectional"))
    )
    (net (code "49") (name "Net-(D42-K)") (class "Default")
      (node (ref "D42") (pin "2") (pinfunction "K_2") (pintype "passive"))
      (node (ref "LD31") (pin "3") (pinfunction "3_3") (pintype "passive"))
      (node (ref "U3") (pin "14") (pinfunction "S5_14") (pintype "bidirectional"))
    )
    (net (code "50") (name "Net-(D43-K)") (class "Default")
      (node (ref "D43") (pin "2") (pinfunction "K_2") (pintype "passive"))
      (node (ref "LD32") (pin "3") (pinfunction "3_3") (pintype "passive"))
      (node (ref "U3") (pin "16") (pinfunction "S6_16") (pintype "bidirectional"))
    )
    (net (code "51") (name "Net-(U3-*RESET{slash}VL)") (class "Default")
      (node (ref "R40") (pin "1") (pinfunction "1_1") (pintype "passive"))
      (node (ref "U3") (pin "23") (pinfunction "*RESET/VL_23") (pintype "bidirectional"))
    )
    (net (code "52") (name "Net-(U3-SDO)") (class "Default")
      (node (ref "TP13") (pin "1") (pinfunction "1_1") (pintype "passive"))
      (node (ref "U3") (pin "22") (pinfunction "SDO_22") (pintype "output"))
    )
    (net (code "53") (name "Net-(U8-*RESET{slash}VL)") (class "Default")
      (node (ref "R39") (pin "1") (pinfunction "1_1") (pintype "passive"))
      (node (ref "U8") (pin "23") (pinfunction "*RESET/VL_23") (pintype "bidirectional"))
    )
    (net (code "54") (name "Net-(U9-*RESET{slash}VL)") (class "Default")
      (node (ref "R42") (pin "1") (pinfunction "1_1") (pintype "passive"))
      (node (ref "U9") (pin "23") (pinfunction "*RESET/VL_23") (pintype "bidirectional"))
    )
    (net (code "55") (name "Net-(U10-*RESET{slash}VL)") (class "Default")
      (node (ref "R44") (pin "1") (pinfunction "1_1") (pintype "passive"))
      (node (ref "U10") (pin "23") (pinfunction "*RESET/VL_23") (pintype "bidirectional"))
    )
  )
)
